# Connector_Sheet1.net
KiCad netlist of a schematic drawn in Altium Designer
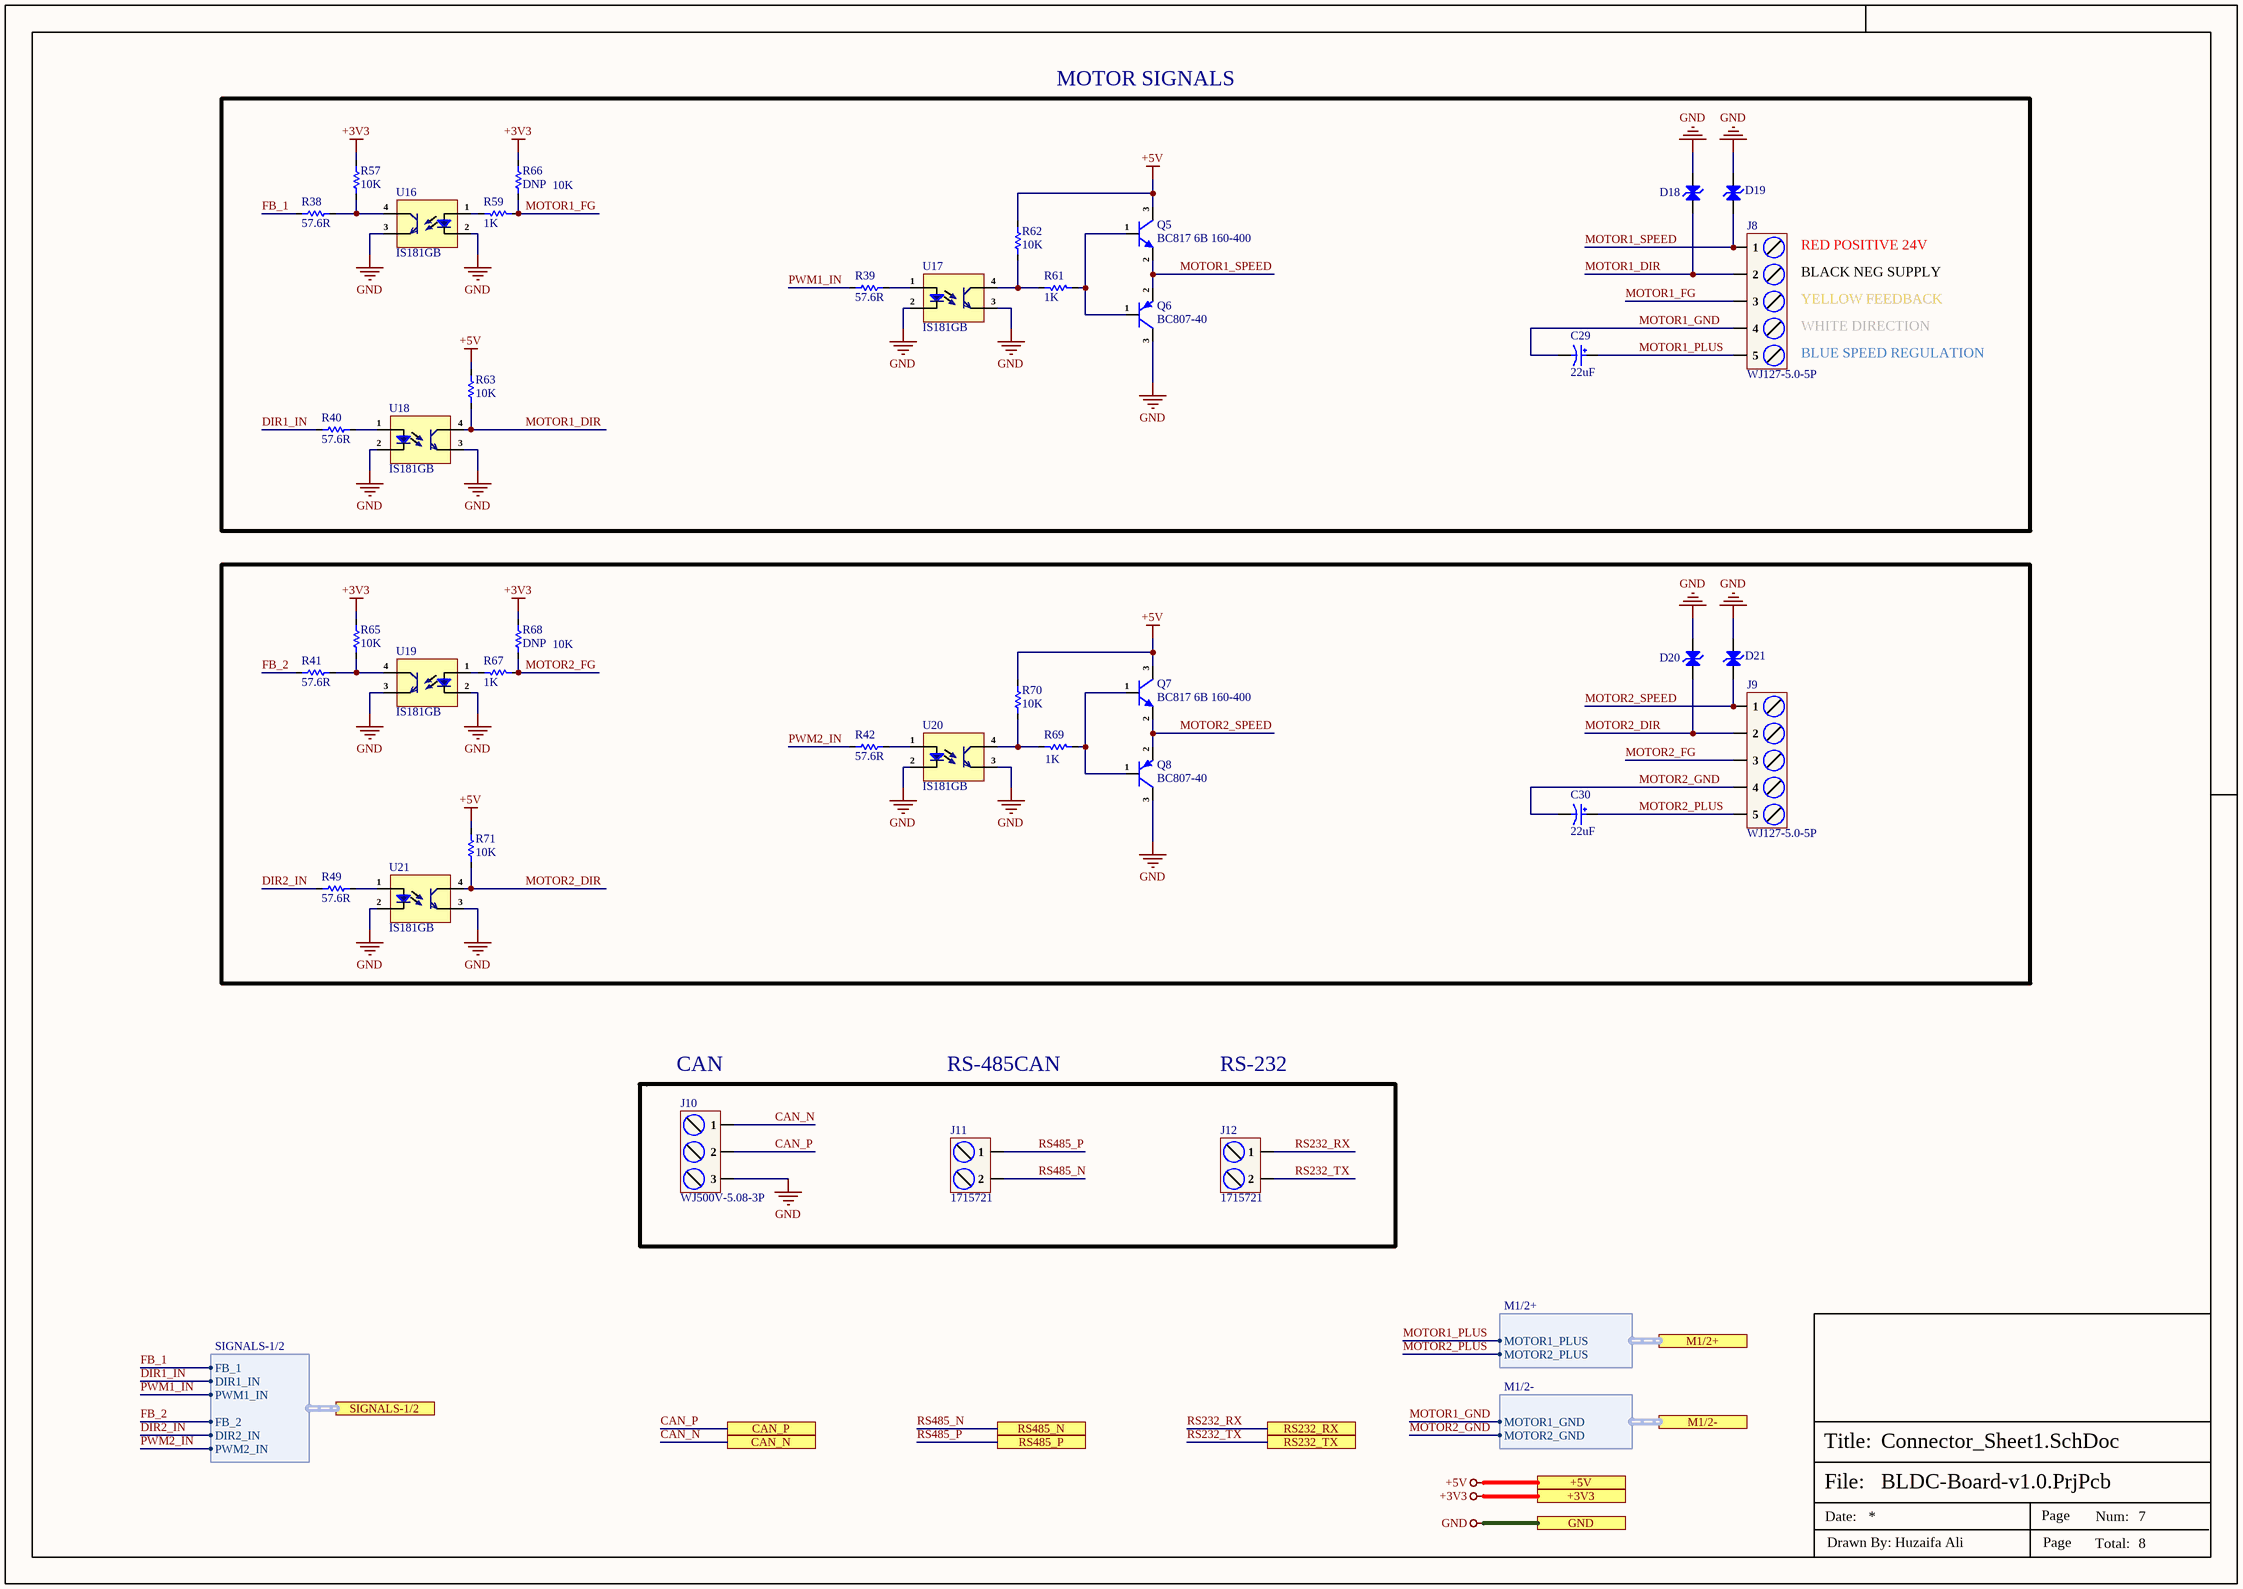
[diagram p0: Connector_Sheet1.SchDoc]

(export (version "E")
  (design (tool "Eeschema 10.0.6"))
  (components
    (comp (ref "C29")
      (value "22uF")
      (footprint "VKMD1652D220MV")
      (description "22uF 200V 320mA@100kHz ±20% SMD,D8xL16.5mm Aluminum Electrolytic Capacitors - SMD ROHS")
      (fields (field (name "MANUFACTURER") "Ymin") (field (name "MANUFACTURER PART NUMBER") "VKMD1652D220MV"))
      (libsource (lib "eSpark Libraries") (part "VKMD1652D220MV"))
    )
    (comp (ref "C30")
      (value "22uF")
      (footprint "VKMD1652D220MV")
      (description "22uF 200V 320mA@100kHz ±20% SMD,D8xL16.5mm Aluminum Electrolytic Capacitors - SMD ROHS")
      (fields (field (name "MANUFACTURER") "Ymin") (field (name "MANUFACTURER PART NUMBER") "VKMD1652D220MV"))
      (libsource (lib "eSpark Libraries") (part "VKMD1652D220MV"))
    )
    (comp (ref "D18")
      (value "ESD5B5.0ST1G")
      (footprint "SOD-523")
      (description "TVS DIODE 5VWM SOD523")
      (fields (field (name "MANUFACTURER") "ON Semiconductor") (field (name "LCSC PART NUMBER") "C93623"))
      (libsource (lib "eSpark Libraries") (part "ESD5B5.0ST1G"))
    )
    (comp (ref "D19")
      (value "ESD5B5.0ST1G")
      (footprint "SOD-523")
      (description "TVS DIODE 5VWM SOD523")
      (fields (field (name "MANUFACTURER") "ON Semiconductor") (field (name "LCSC PART NUMBER") "C93623"))
      (libsource (lib "eSpark Libraries") (part "ESD5B5.0ST1G"))
    )
    (comp (ref "D20")
      (value "ESD5B5.0ST1G")
      (footprint "SOD-523")
      (description "TVS DIODE 5VWM SOD523")
      (fields (field (name "MANUFACTURER") "ON Semiconductor") (field (name "LCSC PART NUMBER") "C93623"))
      (libsource (lib "eSpark Libraries") (part "ESD5B5.0ST1G"))
    )
    (comp (ref "D21")
      (value "ESD5B5.0ST1G")
      (footprint "SOD-523")
      (description "TVS DIODE 5VWM SOD523")
      (fields (field (name "MANUFACTURER") "ON Semiconductor") (field (name "LCSC PART NUMBER") "C93623"))
      (libsource (lib "eSpark Libraries") (part "ESD5B5.0ST1G"))
    )
    (comp (ref "J8")
      (value "WJ127-5.0-5P")
      (footprint "WJ127-5.0-5P")
      (description "1x5P -40℃~+105℃ 15A 250V Green 14~26 Straight pin 5mm 1.5 1 5 Plugin,P=5mm Screw terminal ROHS")
      (fields (field (name "MANUFACTURER") "Ningbo Kangnex Elec") (field (name "LCSC PART NUMBER") "C192780"))
      (libsource (lib "eSpark Libraries") (part "WJ127-5.0-5P"))
    )
    (comp (ref "J9")
      (value "WJ127-5.0-5P")
      (footprint "WJ127-5.0-5P")
      (description "1x5P -40℃~+105℃ 15A 250V Green 14~26 Straight pin 5mm 1.5 1 5 Plugin,P=5mm Screw terminal ROHS")
      (fields (field (name "MANUFACTURER") "Ningbo Kangnex Elec") (field (name "LCSC PART NUMBER") "C192780"))
      (libsource (lib "eSpark Libraries") (part "WJ127-5.0-5P"))
    )
    (comp (ref "J10")
      (value "WJ500V-5.08-3P")
      (footprint "WJ500V-5.08-3P")
      (fields (field (name "MANUFACTURER") "Ningbo Kangnex Elec") (field (name "LCSC PART NUMBER") "C72334"))
      (libsource (lib "eSpark Libraries") (part "WJ500V-5.08-3P"))
    )
    (comp (ref "J11")
      (value "1715721")
      (footprint "1715721")
      (description "TERM BLK 2P SIDE ENT 5.08MM PCB")
      (fields (field (name "MANUFACTURER") "Phoenix Contact"))
      (libsource (lib "eSpark Libraries") (part "1715721"))
    )
    (comp (ref "J12")
      (value "1715721")
      (footprint "1715721")
      (description "TERM BLK 2P SIDE ENT 5.08MM PCB")
      (fields (field (name "MANUFACTURER") "Phoenix Contact"))
      (libsource (lib "eSpark Libraries") (part "1715721"))
    )
    (comp (ref "Q5")
      (value "BC817 6B 160-400")
      (footprint "SOT-23")
      (description "45V 300mW 100@100mA,1V 500mA NPN SOT-23 Bipolar Transistors - BJT ROHS")
      (fields (field (name "MANUFACTURER") "DOWO") (field (name "LCSC PART NUMBER") "C371086"))
      (libsource (lib "eSpark Libraries") (part "BC817 6B 160-400"))
    )
    (comp (ref "Q6")
      (value "BC807-40")
      (footprint "SOT-23")
      (description "45V 310mW 250@100mA,1V 800mA SOT-23 Bipolar (BJT) ROHS")
      (fields (field (name "MANUFACTURER") "KEXIN") (field (name "LCSC PART NUMBER") "C489159"))
      (libsource (lib "eSpark Libraries") (part "BC807-40"))
    )
    (comp (ref "Q7")
      (value "BC817 6B 160-400")
      (footprint "SOT-23")
      (description "45V 300mW 100@100mA,1V 500mA NPN SOT-23 Bipolar Transistors - BJT ROHS")
      (fields (field (name "MANUFACTURER") "DOWO") (field (name "LCSC PART NUMBER") "C371086"))
      (libsource (lib "eSpark Libraries") (part "BC817 6B 160-400"))
    )
    (comp (ref "Q8")
      (value "BC807-40")
      (footprint "SOT-23")
      (description "45V 310mW 250@100mA,1V 800mA SOT-23 Bipolar (BJT) ROHS")
      (fields (field (name "MANUFACTURER") "KEXIN") (field (name "LCSC PART NUMBER") "C489159"))
      (libsource (lib "eSpark Libraries") (part "BC807-40"))
    )
    (comp (ref "R38")
      (value "57.6R")
      (footprint "Res-0402")
      (description "RES SMD 57.6 OHM 1% 1/10W 0402")
      (fields
        (field (name "MANUFACTURER") "Panasonic")
        (field (name "MANUFACTURER PART NUMBER") "ERJ-2RKF57R6X")
      )
      (libsource (lib "eSpark Libraries") (part "ERJ-2RKF57R6X"))
    )
    (comp (ref "R39")
      (value "57.6R")
      (footprint "Res-0402")
      (description "RES SMD 57.6 OHM 1% 1/10W 0402")
      (fields
        (field (name "MANUFACTURER") "Panasonic")
        (field (name "MANUFACTURER PART NUMBER") "ERJ-2RKF57R6X")
      )
      (libsource (lib "eSpark Libraries") (part "ERJ-2RKF57R6X"))
    )
    (comp (ref "R40")
      (value "57.6R")
      (footprint "Res-0402")
      (description "RES SMD 57.6 OHM 1% 1/10W 0402")
      (fields
        (field (name "MANUFACTURER") "Panasonic")
        (field (name "MANUFACTURER PART NUMBER") "ERJ-2RKF57R6X")
      )
      (libsource (lib "eSpark Libraries") (part "ERJ-2RKF57R6X"))
    )
    (comp (ref "R41")
      (value "57.6R")
      (footprint "Res-0402")
      (description "RES SMD 57.6 OHM 1% 1/10W 0402")
      (fields
        (field (name "MANUFACTURER") "Panasonic")
        (field (name "MANUFACTURER PART NUMBER") "ERJ-2RKF57R6X")
      )
      (libsource (lib "eSpark Libraries") (part "ERJ-2RKF57R6X"))
    )
    (comp (ref "R42")
      (value "57.6R")
      (footprint "Res-0402")
      (description "RES SMD 57.6 OHM 1% 1/10W 0402")
      (fields
        (field (name "MANUFACTURER") "Panasonic")
        (field (name "MANUFACTURER PART NUMBER") "ERJ-2RKF57R6X")
      )
      (libsource (lib "eSpark Libraries") (part "ERJ-2RKF57R6X"))
    )
    (comp (ref "R49")
      (value "57.6R")
      (footprint "Res-0402")
      (description "RES SMD 57.6 OHM 1% 1/10W 0402")
      (fields
        (field (name "MANUFACTURER") "Panasonic")
        (field (name "MANUFACTURER PART NUMBER") "ERJ-2RKF57R6X")
      )
      (libsource (lib "eSpark Libraries") (part "ERJ-2RKF57R6X"))
    )
    (comp (ref "R57")
      (value "10K")
      (footprint "Res-0402")
      (description "RES 10K OHM 1% 1/16W 0402")
      (fields
        (field (name "MANUFACTURER") "Yageo")
        (field (name "MANUFACTURER PART NUMBER") "RC0402FR-0710KL")
      )
      (libsource (lib "eSpark Libraries") (part "RC0402FR-0710KL"))
    )
    (comp (ref "R59")
      (value "1K")
      (footprint "Res-0402")
      (description "RES SMD 1K OHM 1% 1/5W 0402")
      (fields
        (field (name "MANUFACTURER") "Vishay Dale")
        (field (name "MANUFACTURER PART NUMBER") "CRCW04021K00FKEDHP")
      )
      (libsource (lib "eSpark Libraries") (part "CRCW04021K00FKEDHP"))
    )
    (comp (ref "R61")
      (value "1K")
      (footprint "Res-0402")
      (description "RES SMD 1K OHM 1% 1/5W 0402")
      (fields
        (field (name "MANUFACTURER") "Vishay Dale")
        (field (name "MANUFACTURER PART NUMBER") "CRCW04021K00FKEDHP")
      )
      (libsource (lib "eSpark Libraries") (part "CRCW04021K00FKEDHP"))
    )
    (comp (ref "R62")
      (value "10K")
      (footprint "Res-0402")
      (description "RES 10K OHM 1% 1/16W 0402")
      (fields
        (field (name "MANUFACTURER") "Yageo")
        (field (name "MANUFACTURER PART NUMBER") "RC0402FR-0710KL")
      )
      (libsource (lib "eSpark Libraries") (part "RC0402FR-0710KL"))
    )
    (comp (ref "R63")
      (value "10K")
      (footprint "Res-0402")
      (description "RES 10K OHM 1% 1/16W 0402")
      (fields
        (field (name "MANUFACTURER") "Yageo")
        (field (name "MANUFACTURER PART NUMBER") "RC0402FR-0710KL")
      )
      (libsource (lib "eSpark Libraries") (part "RC0402FR-0710KL"))
    )
    (comp (ref "R65")
      (value "10K")
      (footprint "Res-0402")
      (description "RES 10K OHM 1% 1/16W 0402")
      (fields
        (field (name "MANUFACTURER") "Yageo")
        (field (name "MANUFACTURER PART NUMBER") "RC0402FR-0710KL")
      )
      (libsource (lib "eSpark Libraries") (part "RC0402FR-0710KL"))
    )
    (comp (ref "R66")
      (value "DNP")
      (footprint "Res-0402")
      (description "RES 10K OHM 1% 1/16W 0402")
      (fields
        (field (name "MANUFACTURER") "Yageo")
        (field (name "MANUFACTURER PART NUMBER") "RC0402FR-0710KL")
      )
      (libsource (lib "eSpark Libraries") (part "RC0402FR-0710KL"))
    )
    (comp (ref "R67")
      (value "1K")
      (footprint "Res-0402")
      (description "RES SMD 1K OHM 1% 1/5W 0402")
      (fields
        (field (name "MANUFACTURER") "Vishay Dale")
        (field (name "MANUFACTURER PART NUMBER") "CRCW04021K00FKEDHP")
      )
      (libsource (lib "eSpark Libraries") (part "CRCW04021K00FKEDHP"))
    )
    (comp (ref "R68")
      (value "DNP")
      (footprint "Res-0402")
      (description "RES 10K OHM 1% 1/16W 0402")
      (fields
        (field (name "MANUFACTURER") "Yageo")
        (field (name "MANUFACTURER PART NUMBER") "RC0402FR-0710KL")
      )
      (libsource (lib "eSpark Libraries") (part "RC0402FR-0710KL"))
    )
    (comp (ref "R69")
      (value "1K")
      (footprint "Res-0402")
      (description "RES SMD 1K OHM 1% 1/5W 0402")
      (fields
        (field (name "MANUFACTURER") "Vishay Dale")
        (field (name "MANUFACTURER PART NUMBER") "CRCW04021K00FKEDHP")
      )
      (libsource (lib "eSpark Libraries") (part "CRCW04021K00FKEDHP"))
    )
    (comp (ref "R70")
      (value "10K")
      (footprint "Res-0402")
      (description "RES 10K OHM 1% 1/16W 0402")
      (fields
        (field (name "MANUFACTURER") "Yageo")
        (field (name "MANUFACTURER PART NUMBER") "RC0402FR-0710KL")
      )
      (libsource (lib "eSpark Libraries") (part "RC0402FR-0710KL"))
    )
    (comp (ref "R71")
      (value "10K")
      (footprint "Res-0402")
      (description "RES 10K OHM 1% 1/16W 0402")
      (fields
        (field (name "MANUFACTURER") "Yageo")
        (field (name "MANUFACTURER PART NUMBER") "RC0402FR-0710KL")
      )
      (libsource (lib "eSpark Libraries") (part "RC0402FR-0710KL"))
    )
    (comp (ref "U16")
      (value "IS181GB")
      (footprint "SOP-4_2.54")
      (description "Optoisolator Transistor Output 3750Vrms 1 Channel")
      (fields (field (name "MANUFACTURER") "Isocom") (field (name "LCSC PART NUMBER") "C84196"))
      (libsource (lib "") (part "IS181GB_1"))
    )
    (comp (ref "U17")
      (value "IS181GB")
      (footprint "SOP-4_2.54")
      (description "Optoisolator Transistor Output 3750Vrms 1 Channel")
      (fields (field (name "MANUFACTURER") "Isocom") (field (name "LCSC PART NUMBER") "C84196"))
      (libsource (lib "eSpark Libraries") (part "IS181GB"))
    )
    (comp (ref "U18")
      (value "IS181GB")
      (footprint "SOP-4_2.54")
      (description "Optoisolator Transistor Output 3750Vrms 1 Channel")
      (fields (field (name "MANUFACTURER") "Isocom") (field (name "LCSC PART NUMBER") "C84196"))
      (libsource (lib "eSpark Libraries") (part "IS181GB"))
    )
    (comp (ref "U19")
      (value "IS181GB")
      (footprint "SOP-4_2.54")
      (description "Optoisolator Transistor Output 3750Vrms 1 Channel")
      (fields (field (name "MANUFACTURER") "Isocom") (field (name "LCSC PART NUMBER") "C84196"))
      (libsource (lib "") (part "IS181GB_1"))
    )
    (comp (ref "U20")
      (value "IS181GB")
      (footprint "SOP-4_2.54")
      (description "Optoisolator Transistor Output 3750Vrms 1 Channel")
      (fields (field (name "MANUFACTURER") "Isocom") (field (name "LCSC PART NUMBER") "C84196"))
      (libsource (lib "eSpark Libraries") (part "IS181GB"))
    )
    (comp (ref "U21")
      (value "IS181GB")
      (footprint "SOP-4_2.54")
      (description "Optoisolator Transistor Output 3750Vrms 1 Channel")
      (fields (field (name "MANUFACTURER") "Isocom") (field (name "LCSC PART NUMBER") "C84196"))
      (libsource (lib "eSpark Libraries") (part "IS181GB"))
    )
  )
  (nets
    (net (code "4") (name "+3V3") (class "Default")
      (node (ref "R57") (pin "2") (pinfunction "2_2") (pintype "passive"))
      (node (ref "R65") (pin "2") (pinfunction "2_2") (pintype "passive"))
      (node (ref "R66") (pin "2") (pinfunction "2_2") (pintype "passive"))
      (node (ref "R68") (pin "2") (pinfunction "2_2") (pintype "passive"))
    )
    (net (code "5") (name "+5V") (class "Default")
      (node (ref "Q5") (pin "3") (pinfunction "C_3") (pintype "passive"))
      (node (ref "Q7") (pin "3") (pinfunction "C_3") (pintype "passive"))
      (node (ref "R62") (pin "1") (pinfunction "1_1") (pintype "passive"))
      (node (ref "R63") (pin "2") (pinfunction "2_2") (pintype "passive"))
      (node (ref "R70") (pin "1") (pinfunction "1_1") (pintype "passive"))
      (node (ref "R71") (pin "2") (pinfunction "2_2") (pintype "passive"))
    )
    (net (code "6") (name "/CAN_N") (class "Default")
      (node (ref "J10") (pin "1") (pinfunction "1_1") (pintype "passive"))
    )
    (net (code "7") (name "/CAN_P") (class "Default")
      (node (ref "J10") (pin "2") (pinfunction "2_2") (pintype "passive"))
    )
    (net (code "8") (name "/DIR1_IN") (class "Default")
      (node (ref "R40") (pin "1") (pinfunction "1_1") (pintype "passive"))
    )
    (net (code "9") (name "/DIR2_IN") (class "Default")
      (node (ref "R49") (pin "1") (pinfunction "1_1") (pintype "passive"))
    )
    (net (code "10") (name "/FB_1") (class "Default")
      (node (ref "R38") (pin "1") (pinfunction "1_1") (pintype "passive"))
    )
    (net (code "11") (name "/FB_2") (class "Default")
      (node (ref "R41") (pin "1") (pinfunction "1_1") (pintype "passive"))
    )
    (net (code "12") (name "/MOTOR1_DIR") (class "Default")
      (node (ref "D18") (pin "1") (pinfunction "A_1") (pintype "passive"))
      (node (ref "J8") (pin "2") (pinfunction "2_2") (pintype "passive"))
      (node (ref "R63") (pin "1") (pinfunction "1_1") (pintype "passive"))
      (node (ref "U18") (pin "4") (pinfunction "C_4") (pintype "passive"))
    )
    (net (code "13") (name "/MOTOR1_FG") (class "Default")
      (node (ref "J8") (pin "3") (pinfunction "3_3") (pintype "passive"))
      (node (ref "R59") (pin "1") (pinfunction "1_1") (pintype "passive"))
      (node (ref "R66") (pin "1") (pinfunction "1_1") (pintype "passive"))
    )
    (net (code "14") (name "/MOTOR1_GND") (class "Default")
      (node (ref "C29") (pin "2") (pintype "passive"))
      (node (ref "J8") (pin "4") (pinfunction "4_4") (pintype "passive"))
    )
    (net (code "15") (name "/MOTOR1_PLUS") (class "Default")
      (node (ref "C29") (pin "1") (pintype "passive"))
      (node (ref "J8") (pin "5") (pinfunction "5_5") (pintype "passive"))
    )
    (net (code "16") (name "/MOTOR1_SPEED") (class "Default")
      (node (ref "D19") (pin "1") (pinfunction "A_1") (pintype "passive"))
      (node (ref "J8") (pin "1") (pinfunction "1_1") (pintype "passive"))
      (node (ref "Q5") (pin "2") (pinfunction "E_2") (pintype "passive"))
      (node (ref "Q6") (pin "2") (pinfunction "E_2") (pintype "passive"))
    )
    (net (code "17") (name "/MOTOR2_DIR") (class "Default")
      (node (ref "D20") (pin "1") (pinfunction "A_1") (pintype "passive"))
      (node (ref "J9") (pin "2") (pinfunction "2_2") (pintype "passive"))
      (node (ref "R71") (pin "1") (pinfunction "1_1") (pintype "passive"))
      (node (ref "U21") (pin "4") (pinfunction "C_4") (pintype "passive"))
    )
    (net (code "18") (name "/MOTOR2_FG") (class "Default")
      (node (ref "J9") (pin "3") (pinfunction "3_3") (pintype "passive"))
      (node (ref "R67") (pin "1") (pinfunction "1_1") (pintype "passive"))
      (node (ref "R68") (pin "1") (pinfunction "1_1") (pintype "passive"))
    )
    (net (code "19") (name "/MOTOR2_GND") (class "Default")
      (node (ref "C30") (pin "2") (pintype "passive"))
      (node (ref "J9") (pin "4") (pinfunction "4_4") (pintype "passive"))
    )
    (net (code "20") (name "/MOTOR2_PLUS") (class "Default")
      (node (ref "C30") (pin "1") (pintype "passive"))
      (node (ref "J9") (pin "5") (pinfunction "5_5") (pintype "passive"))
    )
    (net (code "21") (name "/MOTOR2_SPEED") (class "Default")
      (node (ref "D21") (pin "1") (pinfunction "A_1") (pintype "passive"))
      (node (ref "J9") (pin "1") (pinfunction "1_1") (pintype "passive"))
      (node (ref "Q7") (pin "2") (pinfunction "E_2") (pintype "passive"))
      (node (ref "Q8") (pin "2") (pinfunction "E_2") (pintype "passive"))
    )
    (net (code "22") (name "/PWM1_IN") (class "Default")
      (node (ref "R39") (pin "1") (pinfunction "1_1") (pintype "passive"))
    )
    (net (code "23") (name "/PWM2_IN") (class "Default")
      (node (ref "R42") (pin "1") (pinfunction "1_1") (pintype "passive"))
    )
    (net (code "24") (name "/RS232_RX") (class "Default")
      (node (ref "J12") (pin "1") (pinfunction "1_1") (pintype "passive"))
    )
    (net (code "25") (name "/RS232_TX") (class "Default")
      (node (ref "J12") (pin "2") (pinfunction "2_2") (pintype "passive"))
    )
    (net (code "26") (name "/RS485_N") (class "Default")
      (node (ref "J11") (pin "2") (pinfunction "2_2") (pintype "passive"))
    )
    (net (code "27") (name "/RS485_P") (class "Default")
      (node (ref "J11") (pin "1") (pinfunction "1_1") (pintype "passive"))
    )
    (net (code "31") (name "GND") (class "Default")
      (node (ref "D18") (pin "2") (pinfunction "A_2") (pintype "passive"))
      (node (ref "D19") (pin "2") (pinfunction "A_2") (pintype "passive"))
      (node (ref "D20") (pin "2") (pinfunction "A_2") (pintype "passive"))
      (node (ref "D21") (pin "2") (pinfunction "A_2") (pintype "passive"))
      (node (ref "J10") (pin "3") (pinfunction "3_3") (pintype "passive"))
      (node (ref "Q6") (pin "3") (pinfunction "C_3") (pintype "passive"))
      (node (ref "Q8") (pin "3") (pinfunction "C_3") (pintype "passive"))
      (node (ref "U16") (pin "2") (pinfunction "Ca_2") (pintype "passive"))
      (node (ref "U16") (pin "3") (pinfunction "E_3") (pintype "passive"))
      (node (ref "U17") (pin "2") (pinfunction "Ca_2") (pintype "passive"))
      (node (ref "U17") (pin "3") (pinfunction "E_3") (pintype "passive"))
      (node (ref "U18") (pin "2") (pinfunction "Ca_2") (pintype "passive"))
      (node (ref "U18") (pin "3") (pinfunction "E_3") (pintype "passive"))
      (node (ref "U19") (pin "2") (pinfunction "Ca_2") (pintype "passive"))
      (node (ref "U19") (pin "3") (pinfunction "E_3") (pintype "passive"))
      (node (ref "U20") (pin "2") (pinfunction "Ca_2") (pintype "passive"))
      (node (ref "U20") (pin "3") (pinfunction "E_3") (pintype "passive"))
      (node (ref "U21") (pin "2") (pinfunction "Ca_2") (pintype "passive"))
      (node (ref "U21") (pin "3") (pinfunction "E_3") (pintype "passive"))
    )
    (net (code "32") (name "Net-(Q5-B)") (class "Default")
      (node (ref "Q5") (pin "1") (pinfunction "B_1") (pintype "passive"))
      (node (ref "Q6") (pin "1") (pinfunction "B_1") (pintype "passive"))
      (node (ref "R61") (pin "1") (pinfunction "1_1") (pintype "passive"))
    )
    (net (code "33") (name "Net-(Q7-B)") (class "Default")
      (node (ref "Q7") (pin "1") (pinfunction "B_1") (pintype "passive"))
      (node (ref "Q8") (pin "1") (pinfunction "B_1") (pintype "passive"))
      (node (ref "R69") (pin "1") (pinfunction "1_1") (pintype "passive"))
    )
    (net (code "34") (name "Net-(U16-An)") (class "Default")
      (node (ref "R59") (pin "2") (pinfunction "2_2") (pintype "passive"))
      (node (ref "U16") (pin "1") (pinfunction "An_1") (pintype "passive"))
    )
    (net (code "35") (name "Net-(U16-C)") (class "Default")
      (node (ref "R38") (pin "2") (pinfunction "2_2") (pintype "passive"))
      (node (ref "R57") (pin "1") (pinfunction "1_1") (pintype "passive"))
      (node (ref "U16") (pin "4") (pinfunction "C_4") (pintype "passive"))
    )
    (net (code "36") (name "Net-(U17-An)") (class "Default")
      (node (ref "R39") (pin "2") (pinfunction "2_2") (pintype "passive"))
      (node (ref "U17") (pin "1") (pinfunction "An_1") (pintype "passive"))
    )
    (net (code "37") (name "Net-(U17-C)") (class "Default")
      (node (ref "R61") (pin "2") (pinfunction "2_2") (pintype "passive"))
      (node (ref "R62") (pin "2") (pinfunction "2_2") (pintype "passive"))
      (node (ref "U17") (pin "4") (pinfunction "C_4") (pintype "passive"))
    )
    (net (code "38") (name "Net-(U18-An)") (class "Default")
      (node (ref "R40") (pin "2") (pinfunction "2_2") (pintype "passive"))
      (node (ref "U18") (pin "1") (pinfunction "An_1") (pintype "passive"))
    )
    (net (code "39") (name "Net-(U19-An)") (class "Default")
      (node (ref "R67") (pin "2") (pinfunction "2_2") (pintype "passive"))
      (node (ref "U19") (pin "1") (pinfunction "An_1") (pintype "passive"))
    )
    (net (code "40") (name "Net-(U19-C)") (class "Default")
      (node (ref "R41") (pin "2") (pinfunction "2_2") (pintype "passive"))
      (node (ref "R65") (pin "1") (pinfunction "1_1") (pintype "passive"))
      (node (ref "U19") (pin "4") (pinfunction "C_4") (pintype "passive"))
    )
    (net (code "41") (name "Net-(U20-An)") (class "Default")
      (node (ref "R42") (pin "2") (pinfunction "2_2") (pintype "passive"))
      (node (ref "U20") (pin "1") (pinfunction "An_1") (pintype "passive"))
    )
    (net (code "42") (name "Net-(U20-C)") (class "Default")
      (node (ref "R69") (pin "2") (pinfunction "2_2") (pintype "passive"))
      (node (ref "R70") (pin "2") (pinfunction "2_2") (pintype "passive"))
      (node (ref "U20") (pin "4") (pinfunction "C_4") (pintype "passive"))
    )
    (net (code "43") (name "Net-(U21-An)") (class "Default")
      (node (ref "R49") (pin "2") (pinfunction "2_2") (pintype "passive"))
      (node (ref "U21") (pin "1") (pinfunction "An_1") (pintype "passive"))
    )
  )
)
